# xlr_pegelwandler_v_1_2.net
KiCad netlist of a schematic drawn in EAGLE
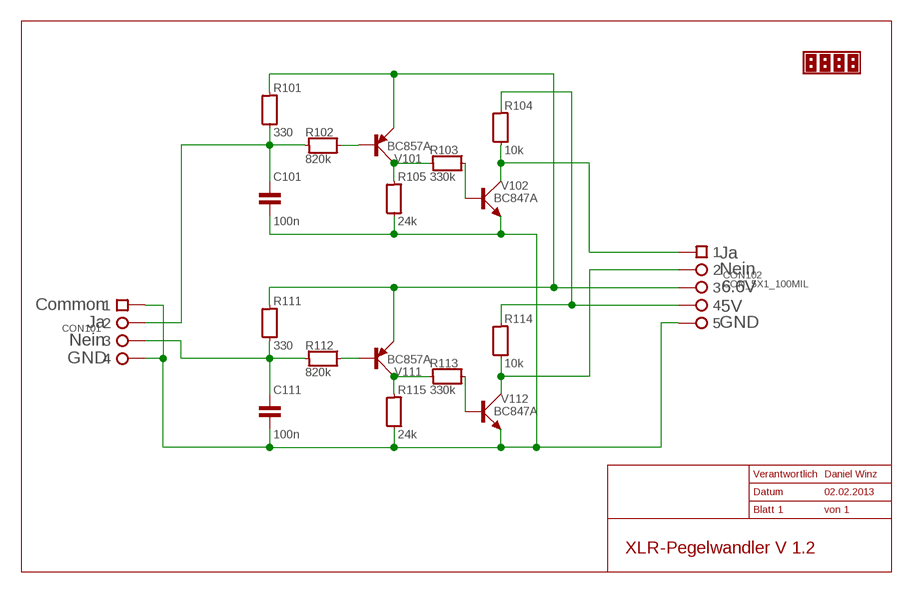
[diagram p0: schematic, sheet 1]

(export (version "E")
  (design (tool "Eeschema 10.0.6"))
  (components
    (comp (ref "C101")
      (value "100n")
      (footprint "eagle-import:C_0805")
      (libsource (lib "eagle-import") (part "KON_V_SMD0805"))
    )
    (comp (ref "C111")
      (value "100n")
      (footprint "eagle-import:C_0805")
      (libsource (lib "eagle-import") (part "KON_V_SMD0805"))
    )
    (comp (ref "CON101")
      (value "XLR_3P+GXLR_NC3MD-V_NEUTRIK")
      (footprint "eagle-import:XLR_NC3MD-V_NEUTRIK")
      (libsource (lib "eagle-import") (part "XLR_3P+GXLR_NC3MD-V_NEUTRIK"))
    )
    (comp (ref "CON102")
      (value "CON_5X1_100MIL")
      (footprint "eagle-import:CON_5X1_100MIL")
      (libsource (lib "eagle-import") (part "CON_5X1_100MIL"))
    )
    (comp (ref "R101")
      (value "330")
      (footprint "eagle-import:R_0805")
      (libsource (lib "eagle-import") (part "WID_V_SMD0805"))
    )
    (comp (ref "R102")
      (value "820k")
      (footprint "eagle-import:R_0805")
      (libsource (lib "eagle-import") (part "WID_H_SMD0805"))
    )
    (comp (ref "R103")
      (value "330k")
      (footprint "eagle-import:R_0805")
      (libsource (lib "eagle-import") (part "WID_H_SMD0805"))
    )
    (comp (ref "R104")
      (value "10k")
      (footprint "eagle-import:R_0805")
      (libsource (lib "eagle-import") (part "WID_V_SMD0805"))
    )
    (comp (ref "R105")
      (value "24k")
      (footprint "eagle-import:R_0805")
      (libsource (lib "eagle-import") (part "WID_V_SMD0805"))
    )
    (comp (ref "R111")
      (value "330")
      (footprint "eagle-import:R_0805")
      (libsource (lib "eagle-import") (part "WID_V_SMD0805"))
    )
    (comp (ref "R112")
      (value "820k")
      (footprint "eagle-import:R_0805")
      (libsource (lib "eagle-import") (part "WID_H_SMD0805"))
    )
    (comp (ref "R113")
      (value "330k")
      (footprint "eagle-import:R_0805")
      (libsource (lib "eagle-import") (part "WID_H_SMD0805"))
    )
    (comp (ref "R114")
      (value "10k")
      (footprint "eagle-import:R_0805")
      (libsource (lib "eagle-import") (part "WID_V_SMD0805"))
    )
    (comp (ref "R115")
      (value "24k")
      (footprint "eagle-import:R_0805")
      (libsource (lib "eagle-import") (part "WID_V_SMD0805"))
    )
    (comp (ref "U$1")
      (value "LP_NUMBER08_SILK_TOP")
      (footprint "eagle-import:LP_NUMBER_SILK_TOP")
      (libsource (lib "eagle-import") (part "LP_NUMBER08_SILK_TOP"))
    )
    (comp (ref "V101")
      (value "BC857A")
      (footprint "eagle-import:SOT23")
      (libsource (lib "eagle-import") (part "PNP_VSOT23"))
    )
    (comp (ref "V102")
      (value "BC847A")
      (footprint "eagle-import:SOT23")
      (libsource (lib "eagle-import") (part "NPN_VSOT23"))
    )
    (comp (ref "V111")
      (value "BC857A")
      (footprint "eagle-import:SOT23")
      (libsource (lib "eagle-import") (part "PNP_VSOT23"))
    )
    (comp (ref "V112")
      (value "BC847A")
      (footprint "eagle-import:SOT23")
      (libsource (lib "eagle-import") (part "NPN_VSOT23"))
    )
  )
  (nets
    (net (code "1") (name "Net-(C101-PadP$1)") (class "Default")
      (node (ref "C101") (pin "P$1") (pinfunction "P$1_P$1") (pintype "bidirectional"))
      (node (ref "CON101") (pin "2") (pinfunction "2_2") (pintype "bidirectional"))
      (node (ref "R101") (pin "P$1") (pinfunction "P$1_P$1") (pintype "bidirectional"))
      (node (ref "R102") (pin "P$1") (pinfunction "P$1_P$1") (pintype "bidirectional"))
    )
    (net (code "2") (name "Net-(C111-PadP$1)") (class "Default")
      (node (ref "C111") (pin "P$1") (pinfunction "P$1_P$1") (pintype "bidirectional"))
      (node (ref "CON101") (pin "3") (pinfunction "3_3") (pintype "bidirectional"))
      (node (ref "R111") (pin "P$1") (pinfunction "P$1_P$1") (pintype "bidirectional"))
      (node (ref "R112") (pin "P$1") (pinfunction "P$1_P$1") (pintype "bidirectional"))
    )
    (net (code "3") (name "Net-(CON101-4)") (class "Default")
      (node (ref "C101") (pin "P$2") (pinfunction "P$2_P$2") (pintype "bidirectional"))
      (node (ref "C111") (pin "P$2") (pinfunction "P$2_P$2") (pintype "bidirectional"))
      (node (ref "CON101") (pin "1") (pinfunction "1_1") (pintype "bidirectional"))
      (node (ref "CON101") (pin "G") (pinfunction "4_G") (pintype "bidirectional"))
      (node (ref "CON102") (pin "P$5") (pinfunction "5_P$5") (pintype "bidirectional"))
      (node (ref "R105") (pin "P$1") (pinfunction "P$1_P$1") (pintype "bidirectional"))
      (node (ref "R115") (pin "P$1") (pinfunction "P$1_P$1") (pintype "bidirectional"))
      (node (ref "V102") (pin "2") (pinfunction "E_2") (pintype "bidirectional"))
      (node (ref "V112") (pin "2") (pinfunction "E_2") (pintype "bidirectional"))
    )
    (net (code "4") (name "Net-(CON102-1)") (class "Default")
      (node (ref "CON102") (pin "P$1") (pinfunction "1_P$1") (pintype "bidirectional"))
      (node (ref "R104") (pin "P$1") (pinfunction "P$1_P$1") (pintype "bidirectional"))
      (node (ref "V102") (pin "3") (pinfunction "C_3") (pintype "bidirectional"))
    )
    (net (code "5") (name "Net-(CON102-2)") (class "Default")
      (node (ref "CON102") (pin "P$2") (pinfunction "2_P$2") (pintype "bidirectional"))
      (node (ref "R114") (pin "P$1") (pinfunction "P$1_P$1") (pintype "bidirectional"))
      (node (ref "V112") (pin "3") (pinfunction "C_3") (pintype "bidirectional"))
    )
    (net (code "6") (name "Net-(CON102-3)") (class "Default")
      (node (ref "CON102") (pin "P$3") (pinfunction "3_P$3") (pintype "bidirectional"))
      (node (ref "R101") (pin "P$2") (pinfunction "P$2_P$2") (pintype "bidirectional"))
      (node (ref "R111") (pin "P$2") (pinfunction "P$2_P$2") (pintype "bidirectional"))
      (node (ref "V101") (pin "2") (pinfunction "P$E_2") (pintype "bidirectional"))
      (node (ref "V111") (pin "2") (pinfunction "P$E_2") (pintype "bidirectional"))
    )
    (net (code "7") (name "Net-(CON102-4)") (class "Default")
      (node (ref "CON102") (pin "P$4") (pinfunction "4_P$4") (pintype "bidirectional"))
      (node (ref "R104") (pin "P$2") (pinfunction "P$2_P$2") (pintype "bidirectional"))
      (node (ref "R114") (pin "P$2") (pinfunction "P$2_P$2") (pintype "bidirectional"))
    )
    (net (code "8") (name "Net-(V101-P$B)") (class "Default")
      (node (ref "R102") (pin "P$2") (pinfunction "P$2_P$2") (pintype "bidirectional"))
      (node (ref "V101") (pin "1") (pinfunction "P$B_1") (pintype "bidirectional"))
    )
    (net (code "9") (name "Net-(V101-P$C)") (class "Default")
      (node (ref "R103") (pin "P$1") (pinfunction "P$1_P$1") (pintype "bidirectional"))
      (node (ref "R105") (pin "P$2") (pinfunction "P$2_P$2") (pintype "bidirectional"))
      (node (ref "V101") (pin "3") (pinfunction "P$C_3") (pintype "bidirectional"))
    )
    (net (code "10") (name "Net-(V102-B)") (class "Default")
      (node (ref "R103") (pin "P$2") (pinfunction "P$2_P$2") (pintype "bidirectional"))
      (node (ref "V102") (pin "1") (pinfunction "B_1") (pintype "bidirectional"))
    )
    (net (code "11") (name "Net-(V111-P$B)") (class "Default")
      (node (ref "R112") (pin "P$2") (pinfunction "P$2_P$2") (pintype "bidirectional"))
      (node (ref "V111") (pin "1") (pinfunction "P$B_1") (pintype "bidirectional"))
    )
    (net (code "12") (name "Net-(V111-P$C)") (class "Default")
      (node (ref "R113") (pin "P$1") (pinfunction "P$1_P$1") (pintype "bidirectional"))
      (node (ref "R115") (pin "P$2") (pinfunction "P$2_P$2") (pintype "bidirectional"))
      (node (ref "V111") (pin "3") (pinfunction "P$C_3") (pintype "bidirectional"))
    )
    (net (code "13") (name "Net-(V112-B)") (class "Default")
      (node (ref "R113") (pin "P$2") (pinfunction "P$2_P$2") (pintype "bidirectional"))
      (node (ref "V112") (pin "1") (pinfunction "B_1") (pintype "bidirectional"))
    )
  )
)
